# Buck_Boost.net
KiCad netlist of a schematic drawn in EAGLE
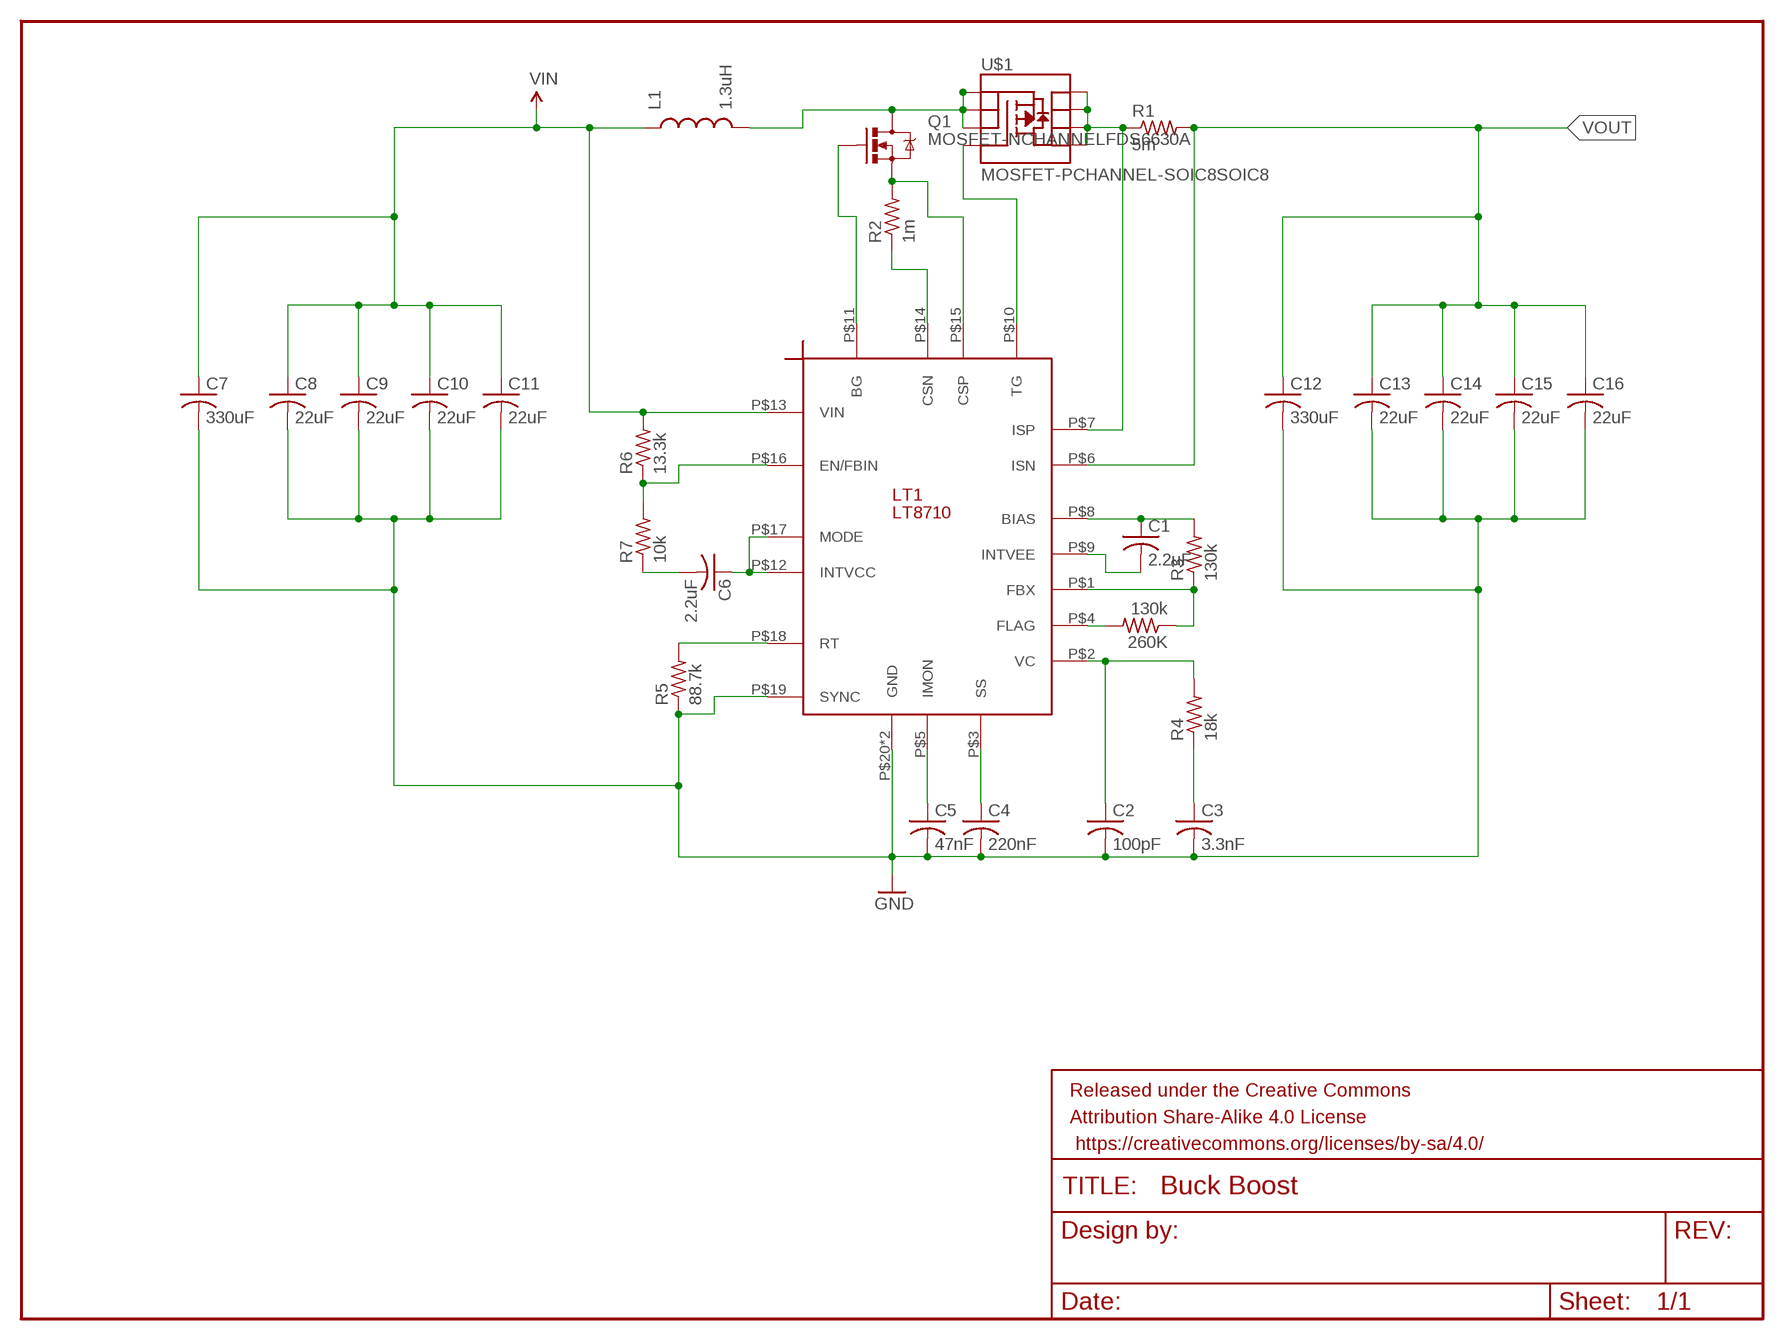
[diagram p0: schematic, sheet 1]

(export (version "E")
  (design (tool "Eeschema 10.0.6"))
  (components
    (comp (ref "260K")
      (value "130k")
      (footprint "eagle-import:R1206")
      (libsource (lib "eagle-import") (part "R-US_R1206"))
    )
    (comp (ref "C1")
      (value "2.2uF")
      (footprint "eagle-import:C1206")
      (libsource (lib "eagle-import") (part "C-USC1206"))
    )
    (comp (ref "C2")
      (value "100pF")
      (footprint "eagle-import:C1206")
      (libsource (lib "eagle-import") (part "C-USC1206"))
    )
    (comp (ref "C3")
      (value "3.3nF")
      (footprint "eagle-import:C1206")
      (libsource (lib "eagle-import") (part "C-USC1206"))
    )
    (comp (ref "C4")
      (value "220nF")
      (footprint "eagle-import:C1206")
      (libsource (lib "eagle-import") (part "C-USC1206"))
    )
    (comp (ref "C5")
      (value "47nF")
      (footprint "eagle-import:C1206")
      (libsource (lib "eagle-import") (part "C-USC1206"))
    )
    (comp (ref "C6")
      (value "2.2uF")
      (footprint "eagle-import:C1206")
      (libsource (lib "eagle-import") (part "C-USC1206"))
    )
    (comp (ref "C7")
      (value "330uF")
      (footprint "eagle-import:C4564")
      (libsource (lib "eagle-import") (part "C-USC4564"))
    )
    (comp (ref "C8")
      (value "22uF")
      (footprint "eagle-import:C1206")
      (libsource (lib "eagle-import") (part "C-USC1206"))
    )
    (comp (ref "C9")
      (value "22uF")
      (footprint "eagle-import:C1206")
      (libsource (lib "eagle-import") (part "C-USC1206"))
    )
    (comp (ref "C10")
      (value "22uF")
      (footprint "eagle-import:C1206")
      (libsource (lib "eagle-import") (part "C-USC1206"))
    )
    (comp (ref "C11")
      (value "22uF")
      (footprint "eagle-import:C1206")
      (libsource (lib "eagle-import") (part "C-USC1206"))
    )
    (comp (ref "C12")
      (value "330uF")
      (footprint "eagle-import:C4564")
      (libsource (lib "eagle-import") (part "C-USC4564"))
    )
    (comp (ref "C13")
      (value "22uF")
      (footprint "eagle-import:C1206")
      (libsource (lib "eagle-import") (part "C-USC1206"))
    )
    (comp (ref "C14")
      (value "22uF")
      (footprint "eagle-import:C1206")
      (libsource (lib "eagle-import") (part "C-USC1206"))
    )
    (comp (ref "C15")
      (value "22uF")
      (footprint "eagle-import:C1206")
      (libsource (lib "eagle-import") (part "C-USC1206"))
    )
    (comp (ref "C16")
      (value "22uF")
      (footprint "eagle-import:C1206")
      (libsource (lib "eagle-import") (part "C-USC1206"))
    )
    (comp (ref "FRAME1")
      (value "FRAME-LETTERNO_PACKAGE")
      (footprint "eagle-import:DUMMY")
      (fields (field (name "DESIGNER") "Nobody"))
      (libsource (lib "eagle-import") (part "FRAME-LETTERNO_PACKAGE"))
    )
    (comp (ref "L1")
      (value "1.3uH")
      (footprint "eagle-import:1210")
      (libsource (lib "eagle-import") (part "INDUCTOR1210"))
    )
    (comp (ref "LT1")
      (value "LT8710")
      (footprint "eagle-import:LT8710")
      (libsource (lib "eagle-import") (part "LT8710"))
    )
    (comp (ref "Q1")
      (value "MOSFET-NCHANNELFDS6630A")
      (footprint "eagle-import:SO08")
      (libsource (lib "eagle-import") (part "MOSFET-NCHANNELFDS6630A"))
    )
    (comp (ref "R1")
      (value "5m")
      (footprint "eagle-import:R1206")
      (libsource (lib "eagle-import") (part "R-US_R1206"))
    )
    (comp (ref "R2")
      (value "1m")
      (footprint "eagle-import:R1206")
      (libsource (lib "eagle-import") (part "R-US_R1206"))
    )
    (comp (ref "R3")
      (value "130k")
      (footprint "eagle-import:R1206")
      (libsource (lib "eagle-import") (part "R-US_R1206"))
    )
    (comp (ref "R4")
      (value "18k")
      (footprint "eagle-import:R1206")
      (libsource (lib "eagle-import") (part "R-US_R1206"))
    )
    (comp (ref "R5")
      (value "88.7k")
      (footprint "eagle-import:R1206")
      (libsource (lib "eagle-import") (part "R-US_R1206"))
    )
    (comp (ref "R6")
      (value "13.3k")
      (footprint "eagle-import:R1206")
      (libsource (lib "eagle-import") (part "R-US_R1206"))
    )
    (comp (ref "R7")
      (value "10k")
      (footprint "eagle-import:R1206")
      (libsource (lib "eagle-import") (part "R-US_R1206"))
    )
    (comp (ref "U$1")
      (value "MOSFET-PCHANNEL-SOIC8SOIC8")
      (footprint "eagle-import:SO08")
      (libsource (lib "eagle-import") (part "MOSFET-PCHANNEL-SOIC8SOIC8"))
    )
  )
  (nets
    (net (code "1") (name "GND") (class "Default")
      (node (ref "C10") (pin "2") (pinfunction "2_2") (pintype "passive"))
      (node (ref "C11") (pin "2") (pinfunction "2_2") (pintype "passive"))
      (node (ref "C12") (pin "2") (pinfunction "2_2") (pintype "passive"))
      (node (ref "C13") (pin "2") (pinfunction "2_2") (pintype "passive"))
      (node (ref "C14") (pin "2") (pinfunction "2_2") (pintype "passive"))
      (node (ref "C15") (pin "2") (pinfunction "2_2") (pintype "passive"))
      (node (ref "C16") (pin "2") (pinfunction "2_2") (pintype "passive"))
      (node (ref "C2") (pin "2") (pinfunction "2_2") (pintype "passive"))
      (node (ref "C3") (pin "2") (pinfunction "2_2") (pintype "passive"))
      (node (ref "C4") (pin "2") (pinfunction "2_2") (pintype "passive"))
      (node (ref "C5") (pin "2") (pinfunction "2_2") (pintype "passive"))
      (node (ref "C7") (pin "2") (pinfunction "2_2") (pintype "passive"))
      (node (ref "C8") (pin "2") (pinfunction "2_2") (pintype "passive"))
      (node (ref "C9") (pin "2") (pinfunction "2_2") (pintype "passive"))
      (node (ref "LT1") (pin "P$19") (pinfunction "SYNC_P$19") (pintype "bidirectional"))
      (node (ref "LT1") (pin "P$20") (pinfunction "GND_P$20") (pintype "bidirectional"))
      (node (ref "LT1") (pin "P$21") (pinfunction "GND_P$21") (pintype "bidirectional"))
      (node (ref "R5") (pin "1") (pinfunction "1_1") (pintype "passive"))
    )
    (net (code "2") (name "Net-(C3-Pad1)") (class "Default")
      (node (ref "C3") (pin "1") (pinfunction "1_1") (pintype "passive"))
      (node (ref "R4") (pin "1") (pinfunction "1_1") (pintype "passive"))
    )
    (net (code "3") (name "Net-(C6-Pad2)") (class "Default")
      (node (ref "C6") (pin "2") (pinfunction "2_2") (pintype "passive"))
      (node (ref "R7") (pin "1") (pinfunction "1_1") (pintype "passive"))
    )
    (net (code "4") (name "Net-(L1-Pad2)") (class "Default")
      (node (ref "L1") (pin "2") (pinfunction "2_2") (pintype "passive"))
      (node (ref "Q1") (pin "5") (pinfunction "D_5") (pintype "passive"))
      (node (ref "Q1") (pin "6") (pinfunction "D_6") (pintype "passive"))
      (node (ref "Q1") (pin "7") (pinfunction "D_7") (pintype "passive"))
      (node (ref "Q1") (pin "8") (pinfunction "D_8") (pintype "passive"))
      (node (ref "U$1") (pin "1") (pinfunction "S_1") (pintype "bidirectional"))
      (node (ref "U$1") (pin "2") (pinfunction "S_2") (pintype "bidirectional"))
      (node (ref "U$1") (pin "3") (pinfunction "S_3") (pintype "bidirectional"))
    )
    (net (code "5") (name "Net-(LT1-BG)") (class "Default")
      (node (ref "LT1") (pin "P$11") (pinfunction "BG_P$11") (pintype "bidirectional"))
      (node (ref "Q1") (pin "4") (pinfunction "G_4") (pintype "passive"))
    )
    (net (code "6") (name "Net-(LT1-BIAS)") (class "Default")
      (node (ref "C1") (pin "1") (pinfunction "1_1") (pintype "passive"))
      (node (ref "LT1") (pin "P$8") (pinfunction "BIAS_P$8") (pintype "bidirectional"))
      (node (ref "R3") (pin "2") (pinfunction "2_2") (pintype "passive"))
    )
    (net (code "7") (name "Net-(LT1-CSN)") (class "Default")
      (node (ref "LT1") (pin "P$14") (pinfunction "CSN_P$14") (pintype "bidirectional"))
      (node (ref "R2") (pin "1") (pinfunction "1_1") (pintype "passive"))
    )
    (net (code "8") (name "Net-(LT1-CSP)") (class "Default")
      (node (ref "LT1") (pin "P$15") (pinfunction "CSP_P$15") (pintype "bidirectional"))
      (node (ref "Q1") (pin "1") (pinfunction "S_1") (pintype "passive"))
      (node (ref "Q1") (pin "2") (pinfunction "S_2") (pintype "passive"))
      (node (ref "Q1") (pin "3") (pinfunction "S_3") (pintype "passive"))
      (node (ref "R2") (pin "2") (pinfunction "2_2") (pintype "passive"))
    )
    (net (code "9") (name "Net-(LT1-EN{slash}FBIN)") (class "Default")
      (node (ref "LT1") (pin "P$16") (pinfunction "EN/FBIN_P$16") (pintype "bidirectional"))
      (node (ref "R6") (pin "1") (pinfunction "1_1") (pintype "passive"))
      (node (ref "R7") (pin "2") (pinfunction "2_2") (pintype "passive"))
    )
    (net (code "10") (name "Net-(LT1-FBX)") (class "Default")
      (node (ref "260K") (pin "1") (pinfunction "1_1") (pintype "passive"))
      (node (ref "LT1") (pin "P$1") (pinfunction "FBX_P$1") (pintype "bidirectional"))
      (node (ref "R3") (pin "1") (pinfunction "1_1") (pintype "passive"))
    )
    (net (code "11") (name "Net-(LT1-FLAG)") (class "Default")
      (node (ref "260K") (pin "2") (pinfunction "2_2") (pintype "passive"))
      (node (ref "LT1") (pin "P$4") (pinfunction "FLAG_P$4") (pintype "bidirectional"))
    )
    (net (code "12") (name "Net-(LT1-IMON)") (class "Default")
      (node (ref "C5") (pin "1") (pinfunction "1_1") (pintype "passive"))
      (node (ref "LT1") (pin "P$5") (pinfunction "IMON_P$5") (pintype "bidirectional"))
    )
    (net (code "13") (name "Net-(LT1-INTVCC)") (class "Default")
      (node (ref "C6") (pin "1") (pinfunction "1_1") (pintype "passive"))
      (node (ref "LT1") (pin "P$12") (pinfunction "INTVCC_P$12") (pintype "bidirectional"))
      (node (ref "LT1") (pin "P$17") (pinfunction "MODE_P$17") (pintype "bidirectional"))
    )
    (net (code "14") (name "Net-(LT1-INTVEE)") (class "Default")
      (node (ref "C1") (pin "2") (pinfunction "2_2") (pintype "passive"))
      (node (ref "LT1") (pin "P$9") (pinfunction "INTVEE_P$9") (pintype "bidirectional"))
    )
    (net (code "15") (name "Net-(LT1-ISP)") (class "Default")
      (node (ref "LT1") (pin "P$7") (pinfunction "ISP_P$7") (pintype "bidirectional"))
      (node (ref "R1") (pin "1") (pinfunction "1_1") (pintype "passive"))
      (node (ref "U$1") (pin "5") (pinfunction "D_5") (pintype "bidirectional"))
      (node (ref "U$1") (pin "6") (pinfunction "D_6") (pintype "bidirectional"))
      (node (ref "U$1") (pin "7") (pinfunction "D_7") (pintype "bidirectional"))
      (node (ref "U$1") (pin "8") (pinfunction "D_8") (pintype "bidirectional"))
    )
    (net (code "16") (name "Net-(LT1-RT)") (class "Default")
      (node (ref "LT1") (pin "P$18") (pinfunction "RT_P$18") (pintype "bidirectional"))
      (node (ref "R5") (pin "2") (pinfunction "2_2") (pintype "passive"))
    )
    (net (code "17") (name "Net-(LT1-SS)") (class "Default")
      (node (ref "C4") (pin "1") (pinfunction "1_1") (pintype "passive"))
      (node (ref "LT1") (pin "P$3") (pinfunction "SS_P$3") (pintype "bidirectional"))
    )
    (net (code "18") (name "Net-(LT1-TG)") (class "Default")
      (node (ref "LT1") (pin "P$10") (pinfunction "TG_P$10") (pintype "bidirectional"))
      (node (ref "U$1") (pin "4") (pinfunction "G_4") (pintype "bidirectional"))
    )
    (net (code "19") (name "Net-(LT1-VC)") (class "Default")
      (node (ref "C2") (pin "1") (pinfunction "1_1") (pintype "passive"))
      (node (ref "LT1") (pin "P$2") (pinfunction "VC_P$2") (pintype "bidirectional"))
      (node (ref "R4") (pin "2") (pinfunction "2_2") (pintype "passive"))
    )
    (net (code "20") (name "VIN") (class "Default")
      (node (ref "C10") (pin "1") (pinfunction "1_1") (pintype "passive"))
      (node (ref "C11") (pin "1") (pinfunction "1_1") (pintype "passive"))
      (node (ref "C7") (pin "1") (pinfunction "1_1") (pintype "passive"))
      (node (ref "C8") (pin "1") (pinfunction "1_1") (pintype "passive"))
      (node (ref "C9") (pin "1") (pinfunction "1_1") (pintype "passive"))
      (node (ref "L1") (pin "1") (pinfunction "1_1") (pintype "passive"))
      (node (ref "LT1") (pin "P$13") (pinfunction "VIN_P$13") (pintype "bidirectional"))
      (node (ref "R6") (pin "2") (pinfunction "2_2") (pintype "passive"))
    )
    (net (code "21") (name "VOUT") (class "Default")
      (node (ref "C12") (pin "1") (pinfunction "1_1") (pintype "passive"))
      (node (ref "C13") (pin "1") (pinfunction "1_1") (pintype "passive"))
      (node (ref "C14") (pin "1") (pinfunction "1_1") (pintype "passive"))
      (node (ref "C15") (pin "1") (pinfunction "1_1") (pintype "passive"))
      (node (ref "C16") (pin "1") (pinfunction "1_1") (pintype "passive"))
      (node (ref "LT1") (pin "P$6") (pinfunction "ISN_P$6") (pintype "bidirectional"))
      (node (ref "R1") (pin "2") (pinfunction "2_2") (pintype "passive"))
    )
  )
)
